# 04_RPI_CAMERA.net
KiCad netlist of a schematic drawn in Altium Designer
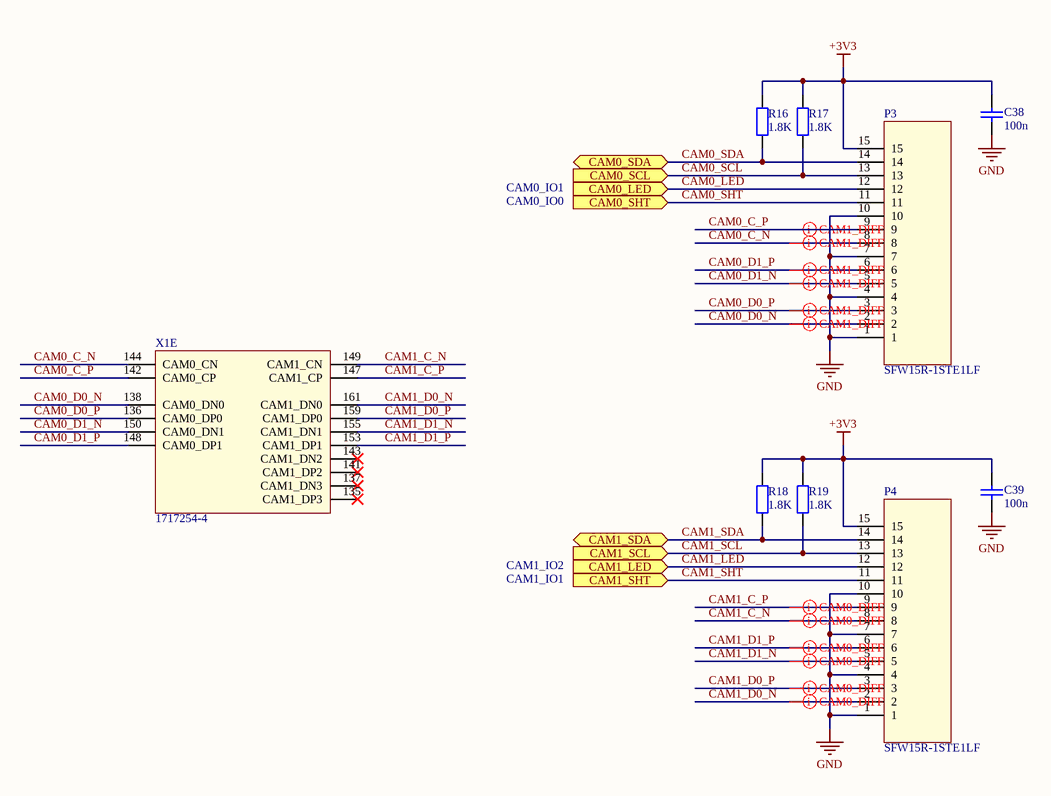
[diagram p0: 04_RPI_CAMERA.SchDoc]

(export (version "E")
  (design (tool "Eeschema 10.0.6"))
  (components
    (comp (ref "C38")
      (value "100n")
      (footprint "C0603_IPC_HD")
      (description "CAP CER 0.1UF 16V X7R 0603")
      (fields
        (field (name "MANUFACTURER") "Samsung Electro-Mechanics")
        (field (name "MANUFACTURER PART NUMBER") "CL10B104KO8NNNC")
      )
      (libsource (lib "alfasat_lib") (part "CL10B104KO8NNNC"))
    )
    (comp (ref "C39")
      (value "100n")
      (footprint "C0603_IPC_HD")
      (description "CAP CER 0.1UF 16V X7R 0603")
      (fields
        (field (name "MANUFACTURER") "Samsung Electro-Mechanics")
        (field (name "MANUFACTURER PART NUMBER") "CL10B104KO8NNNC")
      )
      (libsource (lib "alfasat_lib") (part "CL10B104KO8NNNC"))
    )
    (comp (ref "P3")
      (value "SFW15R-1STE1LF")
      (footprint "SFW15R-1STE1LF")
      (description "CONN FFC BOTTOM 15POS 1.00MM R/A")
      (fields (field (name "MANUFACTURER") "Amphenol ICC (FCI)"))
      (libsource (lib "alfasat_lib") (part "SFW15R-1STE1LF"))
    )
    (comp (ref "P4")
      (value "SFW15R-1STE1LF")
      (footprint "SFW15R-1STE1LF")
      (description "CONN FFC BOTTOM 15POS 1.00MM R/A")
      (fields (field (name "MANUFACTURER") "Amphenol ICC (FCI)"))
      (libsource (lib "alfasat_lib") (part "SFW15R-1STE1LF"))
    )
    (comp (ref "R16")
      (value "1.8K")
      (footprint "R0603_IPC_MD")
      (description "RES SMD 1.8K OHM 5% 1/10W 0603")
      (fields
        (field (name "MANUFACTURER") "Bourns Inc.")
        (field (name "MANUFACTURER PART NUMBER") "CR0603-JW-182ELF")
      )
      (libsource (lib "alfasat_lib") (part "CR0603-JW-182ELF"))
    )
    (comp (ref "R17")
      (value "1.8K")
      (footprint "R0603_IPC_MD")
      (description "RES SMD 1.8K OHM 5% 1/10W 0603")
      (fields
        (field (name "MANUFACTURER") "Bourns Inc.")
        (field (name "MANUFACTURER PART NUMBER") "CR0603-JW-182ELF")
      )
      (libsource (lib "alfasat_lib") (part "CR0603-JW-182ELF"))
    )
    (comp (ref "R18")
      (value "1.8K")
      (footprint "R0603_IPC_MD")
      (description "RES SMD 1.8K OHM 5% 1/10W 0603")
      (fields
        (field (name "MANUFACTURER") "Bourns Inc.")
        (field (name "MANUFACTURER PART NUMBER") "CR0603-JW-182ELF")
      )
      (libsource (lib "alfasat_lib") (part "CR0603-JW-182ELF"))
    )
    (comp (ref "R19")
      (value "1.8K")
      (footprint "R0603_IPC_MD")
      (description "RES SMD 1.8K OHM 5% 1/10W 0603")
      (fields
        (field (name "MANUFACTURER") "Bourns Inc.")
        (field (name "MANUFACTURER PART NUMBER") "CR0603-JW-182ELF")
      )
      (libsource (lib "alfasat_lib") (part "CR0603-JW-182ELF"))
    )
    (comp (ref "X1")
      (value "1717254-4")
      (footprint "1717254-1")
      (description "CONN SKT SODIMM 200POS R/A SMD")
      (fields (field (name "MANUFACTURER") "TE Connectivity AMP Connectors"))
      (libsource (lib "alfasat_lib") (part "Raspberry CM Connector"))
    )
  )
  (nets
    (net (code "1") (name "+3V3") (class "Default")
      (node (ref "C38") (pin "2") (pinfunction "2_2") (pintype "passive"))
      (node (ref "C39") (pin "2") (pinfunction "2_2") (pintype "passive"))
      (node (ref "P3") (pin "15") (pinfunction "15_15") (pintype "passive"))
      (node (ref "P4") (pin "15") (pinfunction "15_15") (pintype "passive"))
      (node (ref "R16") (pin "2") (pinfunction "2_2") (pintype "passive"))
      (node (ref "R17") (pin "2") (pinfunction "2_2") (pintype "passive"))
      (node (ref "R18") (pin "2") (pinfunction "2_2") (pintype "passive"))
      (node (ref "R19") (pin "2") (pinfunction "2_2") (pintype "passive"))
    )
    (net (code "2") (name "/CAM0_C_N") (class "Default")
      (node (ref "P3") (pin "8") (pinfunction "8_8") (pintype "passive"))
      (node (ref "X1") (pin "144") (pinfunction "CAM0_CN_144") (pintype "passive"))
    )
    (net (code "3") (name "/CAM0_C_P") (class "Default")
      (node (ref "P3") (pin "9") (pinfunction "9_9") (pintype "passive"))
      (node (ref "X1") (pin "142") (pinfunction "CAM0_CP_142") (pintype "passive"))
    )
    (net (code "4") (name "/CAM0_D0_N") (class "Default")
      (node (ref "P3") (pin "2") (pinfunction "2_2") (pintype "passive"))
      (node (ref "X1") (pin "138") (pinfunction "CAM0_DN0_138") (pintype "passive"))
    )
    (net (code "5") (name "/CAM0_D0_P") (class "Default")
      (node (ref "P3") (pin "3") (pinfunction "3_3") (pintype "passive"))
      (node (ref "X1") (pin "136") (pinfunction "CAM0_DP0_136") (pintype "passive"))
    )
    (net (code "6") (name "/CAM0_D1_N") (class "Default")
      (node (ref "P3") (pin "5") (pinfunction "5_5") (pintype "passive"))
      (node (ref "X1") (pin "150") (pinfunction "CAM0_DN1_150") (pintype "passive"))
    )
    (net (code "7") (name "/CAM0_D1_P") (class "Default")
      (node (ref "P3") (pin "6") (pinfunction "6_6") (pintype "passive"))
      (node (ref "X1") (pin "148") (pinfunction "CAM0_DP1_148") (pintype "passive"))
    )
    (net (code "8") (name "/CAM0_LED") (class "Default")
      (node (ref "P3") (pin "12") (pinfunction "12_12") (pintype "passive"))
    )
    (net (code "9") (name "/CAM0_SCL") (class "Default")
      (node (ref "P3") (pin "13") (pinfunction "13_13") (pintype "passive"))
      (node (ref "R17") (pin "1") (pinfunction "1_1") (pintype "passive"))
    )
    (net (code "10") (name "/CAM0_SDA") (class "Default")
      (node (ref "P3") (pin "14") (pinfunction "14_14") (pintype "passive"))
      (node (ref "R16") (pin "1") (pinfunction "1_1") (pintype "passive"))
    )
    (net (code "11") (name "/CAM0_SHT") (class "Default")
      (node (ref "P3") (pin "11") (pinfunction "11_11") (pintype "passive"))
    )
    (net (code "12") (name "/CAM1_C_N") (class "Default")
      (node (ref "P4") (pin "8") (pinfunction "8_8") (pintype "passive"))
      (node (ref "X1") (pin "149") (pinfunction "CAM1_CN_149") (pintype "passive"))
    )
    (net (code "13") (name "/CAM1_C_P") (class "Default")
      (node (ref "P4") (pin "9") (pinfunction "9_9") (pintype "passive"))
      (node (ref "X1") (pin "147") (pinfunction "CAM1_CP_147") (pintype "passive"))
    )
    (net (code "14") (name "/CAM1_D0_N") (class "Default")
      (node (ref "P4") (pin "2") (pinfunction "2_2") (pintype "passive"))
      (node (ref "X1") (pin "161") (pinfunction "CAM1_DN0_161") (pintype "passive"))
    )
    (net (code "15") (name "/CAM1_D0_P") (class "Default")
      (node (ref "P4") (pin "3") (pinfunction "3_3") (pintype "passive"))
      (node (ref "X1") (pin "159") (pinfunction "CAM1_DP0_159") (pintype "passive"))
    )
    (net (code "16") (name "/CAM1_D1_N") (class "Default")
      (node (ref "P4") (pin "5") (pinfunction "5_5") (pintype "passive"))
      (node (ref "X1") (pin "155") (pinfunction "CAM1_DN1_155") (pintype "passive"))
    )
    (net (code "17") (name "/CAM1_D1_P") (class "Default")
      (node (ref "P4") (pin "6") (pinfunction "6_6") (pintype "passive"))
      (node (ref "X1") (pin "153") (pinfunction "CAM1_DP1_153") (pintype "passive"))
    )
    (net (code "18") (name "/CAM1_LED") (class "Default")
      (node (ref "P4") (pin "12") (pinfunction "12_12") (pintype "passive"))
    )
    (net (code "19") (name "/CAM1_SCL") (class "Default")
      (node (ref "P4") (pin "13") (pinfunction "13_13") (pintype "passive"))
      (node (ref "R19") (pin "1") (pinfunction "1_1") (pintype "passive"))
    )
    (net (code "20") (name "/CAM1_SDA") (class "Default")
      (node (ref "P4") (pin "14") (pinfunction "14_14") (pintype "passive"))
      (node (ref "R18") (pin "1") (pinfunction "1_1") (pintype "passive"))
    )
    (net (code "21") (name "/CAM1_SHT") (class "Default")
      (node (ref "P4") (pin "11") (pinfunction "11_11") (pintype "passive"))
    )
    (net (code "22") (name "GND") (class "Default")
      (node (ref "C38") (pin "1") (pinfunction "1_1") (pintype "passive"))
      (node (ref "C39") (pin "1") (pinfunction "1_1") (pintype "passive"))
      (node (ref "P3") (pin "1") (pinfunction "1_1") (pintype "passive"))
      (node (ref "P3") (pin "10") (pinfunction "10_10") (pintype "passive"))
      (node (ref "P3") (pin "4") (pinfunction "4_4") (pintype "passive"))
      (node (ref "P3") (pin "7") (pinfunction "7_7") (pintype "passive"))
      (node (ref "P4") (pin "1") (pinfunction "1_1") (pintype "passive"))
      (node (ref "P4") (pin "10") (pinfunction "10_10") (pintype "passive"))
      (node (ref "P4") (pin "4") (pinfunction "4_4") (pintype "passive"))
      (node (ref "P4") (pin "7") (pinfunction "7_7") (pintype "passive"))
    )
    (net (code "23") (name "unconnected-(X1E-CAM1_DN2-Pad143)") (class "Default")
      (node (ref "X1") (pin "143") (pinfunction "CAM1_DN2_143") (pintype "passive+no_connect"))
    )
    (net (code "24") (name "unconnected-(X1E-CAM1_DN3-Pad137)") (class "Default")
      (node (ref "X1") (pin "137") (pinfunction "CAM1_DN3_137") (pintype "passive+no_connect"))
    )
    (net (code "25") (name "unconnected-(X1E-CAM1_DP2-Pad141)") (class "Default")
      (node (ref "X1") (pin "141") (pinfunction "CAM1_DP2_141") (pintype "passive+no_connect"))
    )
    (net (code "26") (name "unconnected-(X1E-CAM1_DP3-Pad135)") (class "Default")
      (node (ref "X1") (pin "135") (pinfunction "CAM1_DP3_135") (pintype "passive+no_connect"))
    )
  )
)
